# GPS.net
KiCad netlist of a schematic drawn in Altium Designer
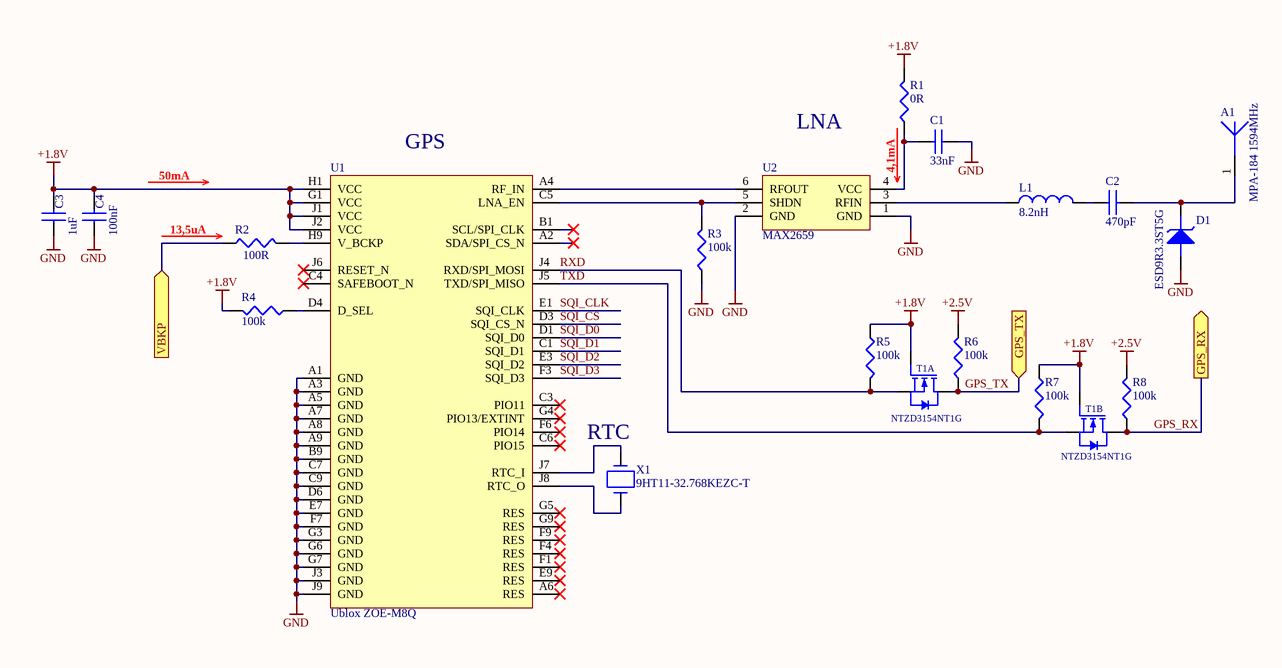
[diagram p0: GPS.SchDoc]

(export (version "E")
  (design (tool "Eeschema 10.0.6"))
  (components
    (comp (ref "A1")
      (value "MPA-184 1594MHz")
      (footprint "MPA-184")
      (description "Antennas Passive GPS/GLONASS Patch Antenna")
      (fields (field (name "MANUFACTURER") "Antenova") (field (name "MANUFACTURER PART NUMBER") "SR42I010-R"))
      (libsource (lib "Passive") (part "ANT - MAXTENA MPA-184 1594MHz"))
    )
    (comp (ref "C1")
      (value "33nF")
      (footprint "CAP0402")
      (description "33 pF, 16 V,  5%, C0G / NP0, MC Series")
      (fields
        (field (name "MANUFACTURER") "Multicomp")
        (field (name "MANUFACTURER PART NUMBER") "MC0402N330J160CT")
      )
      (libsource (lib "Passive") (part "C - 33pF/0402"))
    )
    (comp (ref "C2")
      (value "470pF")
      (footprint "CAP0402")
      (description "470 pF, 50 V, 0402 [1005 Metric], ± 10%, X7R, GRT Series")
      (fields
        (field (name "MANUFACTURER") "Murata")
        (field (name "MANUFACTURER PART NUMBER") "GRT155R71H471KE01D")
      )
      (libsource (lib "Passive") (part "C - 470pF/0402"))
    )
    (comp (ref "C3")
      (value "1uF")
      (footprint "CAP0402")
      (description "CAP CER 1UF 10V 20% X5R 0402")
      (fields
        (field (name "MANUFACTURER") "Murata")
        (field (name "MANUFACTURER PART NUMBER") "GRM155R61A105ME15D")
      )
      (libsource (lib "Passive") (part "C - 1uF/0402"))
    )
    (comp (ref "C4")
      (value "100nF")
      (footprint "CAP0402")
      (description "0.1 F, 16 V,  5%, X5R, MC Series")
      (fields
        (field (name "MANUFACTURER") "Multicomp")
        (field (name "MANUFACTURER PART NUMBER") "MC0402X104J160CT")
      )
      (libsource (lib "Passive") (part "C - 100nF/0402"))
    )
    (comp (ref "D1")
      (value "ESD9R3.3ST5G")
      (footprint "SOD-923")
      (description "TVS Diode, ESD9R Series, Unidirectional, 3.3 V, 7.8 V")
      (fields
        (field (name "MANUFACTURER") "DIODES INC.")
        (field (name "MANUFACTURER PART NUMBER") "1N4148W-7-F.")
      )
      (libsource (lib "Active") (part "D_TVS - ESD9R3.3ST5G"))
    )
    (comp (ref "L1")
      (value "8.2nH")
      (footprint "IND0402")
      (description "High Frequency Inductor, 8.2 nH, LQG15HN Series, 300 mA, 0402 [1005 Metric], Multilayer, 0.33 ohm")
      (fields
        (field (name "MANUFACTURER") "Murata")
        (field (name "MANUFACTURER PART NUMBER") "LQG15HS33NJ02D")
      )
      (libsource (lib "Passive") (part "L - 33nH/0402"))
    )
    (comp (ref "R1")
      (value "0R")
      (footprint "RES0402")
      (description "RESISTOR, 0402, 0R, ANTI SULFURATION")
      (fields
        (field (name "MANUFACTURER") "Multicomp")
        (field (name "MANUFACTURER PART NUMBER") "MCMR04X000PTL")
      )
      (libsource (lib "Passive") (part "R - 0R/0402"))
    )
    (comp (ref "R2")
      (value "100R")
      (footprint "RES0402")
      (description "100 ohm, 50 V, 0402 [1005 Metric], 62.5 mW,  1%")
      (fields
        (field (name "MANUFACTURER") "Multicomp")
        (field (name "MANUFACTURER PART NUMBER") "MCMR04X1000FTL")
      )
      (libsource (lib "Passive") (part "R - 100R/0402"))
    )
    (comp (ref "R3")
      (value "100k")
      (footprint "RES0402")
      (description "100KOHM, 1%, 0.0625W")
      (fields
        (field (name "MANUFACTURER") "Multicomp")
        (field (name "MANUFACTURER PART NUMBER") "MCWR04X1003FTL")
      )
      (libsource (lib "Passive") (part "R - 100k/0402"))
    )
    (comp (ref "R4")
      (value "100k")
      (footprint "RES0402")
      (description "100KOHM, 1%, 0.0625W")
      (fields
        (field (name "MANUFACTURER") "Multicomp")
        (field (name "MANUFACTURER PART NUMBER") "MCWR04X1003FTL")
      )
      (libsource (lib "Passive") (part "R - 100k/0402"))
    )
    (comp (ref "R5")
      (value "100k")
      (footprint "RES0402")
      (description "100KOHM, 1%, 0.0625W")
      (fields
        (field (name "MANUFACTURER") "Multicomp")
        (field (name "MANUFACTURER PART NUMBER") "MCWR04X1003FTL")
      )
      (libsource (lib "Passive") (part "R - 100k/0402"))
    )
    (comp (ref "R6")
      (value "100k")
      (footprint "RES0402")
      (description "100KOHM, 1%, 0.0625W")
      (fields
        (field (name "MANUFACTURER") "Multicomp")
        (field (name "MANUFACTURER PART NUMBER") "MCWR04X1003FTL")
      )
      (libsource (lib "Passive") (part "R - 100k/0402"))
    )
    (comp (ref "R7")
      (value "100k")
      (footprint "RES0402")
      (description "100KOHM, 1%, 0.0625W")
      (fields
        (field (name "MANUFACTURER") "Multicomp")
        (field (name "MANUFACTURER PART NUMBER") "MCWR04X1003FTL")
      )
      (libsource (lib "Passive") (part "R - 100k/0402"))
    )
    (comp (ref "R8")
      (value "100k")
      (footprint "RES0402")
      (description "100KOHM, 1%, 0.0625W")
      (fields
        (field (name "MANUFACTURER") "Multicomp")
        (field (name "MANUFACTURER PART NUMBER") "MCWR04X1003FTL")
      )
      (libsource (lib "Passive") (part "R - 100k/0402"))
    )
    (comp (ref "T1")
      (value "NTZD3154NT1G")
      (footprint "SOT-563")
      (description "Dual MOSFET, Dual N Channel, 540 mA, 20 V, 0.4 ohm, 4.5 V, 1 V")
      (fields (field (name "AUTHOR") "Ciril Golob"))
      (libsource (lib "Active") (part "T_M - NTZD3154NT1G"))
    )
    (comp (ref "U1")
      (value "Ublox ZOE-M8Q")
      (footprint "S-LGA51")
      (description "ZOE-M8 RF Receiver BeiDou, Galileo, GLONASS, GNSS, GPS -160dBm")
      (fields (field (name "MANUFACTURER") "u-blox") (field (name "MANUFACTURER PART NUMBER") "MAX-M8Q-0"))
      (libsource (lib "Active") (part "RF - UBLOX-ZOE-M8B"))
    )
    (comp (ref "U2")
      (value "MAX2659")
      (footprint "uDFN-6")
      (description "RF Amplifier, GPS / GNSS, 20.5 dB Gain / 0.8 dB Noise, 1575.42 MHz, 1.6 V to 3.3 V Supply")
      (fields (field (name "MANUFACTURER") "u-blox") (field (name "MANUFACTURER PART NUMBER") "MAX-M8Q-0"))
      (libsource (lib "Active") (part "RF - MAX2659"))
    )
    (comp (ref "X1")
      (value "9HT11-32.768KEZC-T")
      (footprint "9HT11")
      (description "Crystal, 32.768 kHz, SMD, 2mm x 1.2mm, 9 pF, 10 ppm, 9HT11 Series")
      (fields (field (name "MANUFACTURER") "IQD") (field (name "MANUFACTURER PART NUMBER") "LFXTAL009678"))
      (libsource (lib "Passive") (part "X - 9HT11-32.768KEZC-T"))
    )
  )
  (nets
    (net (code "1") (name "+1.8V") (class "Default")
      (node (ref "C3") (pin "2") (pinfunction "2_2") (pintype "passive"))
      (node (ref "C4") (pin "2") (pinfunction "2_2") (pintype "passive"))
      (node (ref "R1") (pin "2") (pinfunction "2_2") (pintype "passive"))
      (node (ref "R4") (pin "2") (pinfunction "2_2") (pintype "passive"))
      (node (ref "R5") (pin "1") (pinfunction "1_1") (pintype "passive"))
      (node (ref "R7") (pin "1") (pinfunction "1_1") (pintype "passive"))
      (node (ref "T1") (pin "2") (pinfunction "G1_2") (pintype "passive"))
      (node (ref "T1") (pin "5") (pinfunction "G2_5") (pintype "passive"))
      (node (ref "U1") (pin "G1") (pinfunction "VCC_G1") (pintype "passive"))
      (node (ref "U1") (pin "H1") (pinfunction "VCC_H1") (pintype "passive"))
      (node (ref "U1") (pin "J1") (pinfunction "VCC_J1") (pintype "passive"))
      (node (ref "U1") (pin "J2") (pinfunction "VCC_J2") (pintype "passive"))
    )
    (net (code "2") (name "+2.5V") (class "Default")
      (node (ref "R6") (pin "2") (pinfunction "2_2") (pintype "passive"))
      (node (ref "R8") (pin "2") (pinfunction "2_2") (pintype "passive"))
    )
    (net (code "3") (name "/GPS_RX") (class "Default")
      (node (ref "R8") (pin "1") (pinfunction "1_1") (pintype "passive"))
      (node (ref "T1") (pin "3") (pinfunction "D2_3") (pintype "passive"))
    )
    (net (code "4") (name "/GPS_TX") (class "Default")
      (node (ref "R6") (pin "1") (pinfunction "1_1") (pintype "passive"))
      (node (ref "T1") (pin "6") (pinfunction "D1_6") (pintype "passive"))
    )
    (net (code "5") (name "/RXD") (class "Default")
      (node (ref "R5") (pin "2") (pinfunction "2_2") (pintype "passive"))
      (node (ref "T1") (pin "1") (pinfunction "S1_1") (pintype "passive"))
      (node (ref "U1") (pin "J4") (pinfunction "RXD/SPI_MOSI_J4") (pintype "passive"))
    )
    (net (code "6") (name "/SQI_CLK") (class "Default")
      (node (ref "U1") (pin "E1") (pinfunction "SQI_CLK_E1") (pintype "passive"))
    )
    (net (code "7") (name "/SQI_CS") (class "Default")
      (node (ref "U1") (pin "D3") (pinfunction "SQI_CS_N_D3") (pintype "passive"))
    )
    (net (code "8") (name "/SQI_D0") (class "Default")
      (node (ref "U1") (pin "D1") (pinfunction "SQI_D0_D1") (pintype "passive"))
    )
    (net (code "9") (name "/SQI_D1") (class "Default")
      (node (ref "U1") (pin "C1") (pinfunction "SQI_D1_C1") (pintype "passive"))
    )
    (net (code "10") (name "/SQI_D2") (class "Default")
      (node (ref "U1") (pin "E3") (pinfunction "SQI_D2_E3") (pintype "passive"))
    )
    (net (code "11") (name "/SQI_D3") (class "Default")
      (node (ref "U1") (pin "F3") (pinfunction "SQI_D3_F3") (pintype "passive"))
    )
    (net (code "12") (name "/TXD") (class "Default")
      (node (ref "R7") (pin "2") (pinfunction "2_2") (pintype "passive"))
      (node (ref "T1") (pin "4") (pinfunction "S2_4") (pintype "passive"))
      (node (ref "U1") (pin "J5") (pinfunction "TXD/SPI_MISO_J5") (pintype "passive"))
    )
    (net (code "13") (name "/VBKP") (class "Default")
      (node (ref "R2") (pin "1") (pinfunction "1_1") (pintype "passive"))
    )
    (net (code "14") (name "GND") (class "Default")
      (node (ref "C1") (pin "1") (pinfunction "1_1") (pintype "passive"))
      (node (ref "C3") (pin "1") (pinfunction "1_1") (pintype "passive"))
      (node (ref "C4") (pin "1") (pinfunction "1_1") (pintype "passive"))
      (node (ref "D1") (pin "A") (pinfunction "ANODE_A") (pintype "passive"))
      (node (ref "R3") (pin "1") (pinfunction "1_1") (pintype "passive"))
      (node (ref "U1") (pin "A1") (pinfunction "GND_A1") (pintype "passive"))
      (node (ref "U1") (pin "A3") (pinfunction "GND_A3") (pintype "passive"))
      (node (ref "U1") (pin "A5") (pinfunction "GND_A5") (pintype "passive"))
      (node (ref "U1") (pin "A7") (pinfunction "GND_A7") (pintype "passive"))
      (node (ref "U1") (pin "A8") (pinfunction "GND_A8") (pintype "passive"))
      (node (ref "U1") (pin "A9") (pinfunction "GND_A9") (pintype "passive"))
      (node (ref "U1") (pin "B9") (pinfunction "GND_B9") (pintype "passive"))
      (node (ref "U1") (pin "C7") (pinfunction "GND_C7") (pintype "passive"))
      (node (ref "U1") (pin "C9") (pinfunction "GND_C9") (pintype "passive"))
      (node (ref "U1") (pin "D6") (pinfunction "GND_D6") (pintype "passive"))
      (node (ref "U1") (pin "E7") (pinfunction "GND_E7") (pintype "passive"))
      (node (ref "U1") (pin "F7") (pinfunction "GND_F7") (pintype "passive"))
      (node (ref "U1") (pin "G3") (pinfunction "GND_G3") (pintype "passive"))
      (node (ref "U1") (pin "G6") (pinfunction "GND_G6") (pintype "passive"))
      (node (ref "U1") (pin "G7") (pinfunction "GND_G7") (pintype "passive"))
      (node (ref "U1") (pin "J3") (pinfunction "GND_J3") (pintype "passive"))
      (node (ref "U1") (pin "J9") (pinfunction "GND_J9") (pintype "passive"))
      (node (ref "U2") (pin "1") (pinfunction "GND_1") (pintype "passive"))
      (node (ref "U2") (pin "2") (pinfunction "GND_2") (pintype "passive"))
    )
    (net (code "15") (name "Net-(A1-ANT)") (class "Default")
      (node (ref "A1") (pin "1") (pinfunction "ANT_1") (pintype "passive"))
      (node (ref "C2") (pin "2") (pinfunction "2_2") (pintype "passive"))
      (node (ref "D1") (pin "K") (pinfunction "cathode_K") (pintype "passive"))
    )
    (net (code "16") (name "Net-(C2-Pad1)") (class "Default")
      (node (ref "C2") (pin "1") (pinfunction "1_1") (pintype "passive"))
      (node (ref "L1") (pin "2") (pinfunction "2_2") (pintype "passive"))
    )
    (net (code "17") (name "Net-(U1-D_SEL)") (class "Default")
      (node (ref "R4") (pin "1") (pinfunction "1_1") (pintype "passive"))
      (node (ref "U1") (pin "D4") (pinfunction "D_SEL_D4") (pintype "passive"))
    )
    (net (code "18") (name "Net-(U1-LNA_EN)") (class "Default")
      (node (ref "R3") (pin "2") (pinfunction "2_2") (pintype "passive"))
      (node (ref "U1") (pin "C5") (pinfunction "LNA_EN_C5") (pintype "passive"))
      (node (ref "U2") (pin "5") (pinfunction "SHDN_5") (pintype "passive"))
    )
    (net (code "19") (name "Net-(U1-RF_IN)") (class "Default")
      (node (ref "U1") (pin "A4") (pinfunction "RF_IN_A4") (pintype "passive"))
      (node (ref "U2") (pin "6") (pinfunction "RFOUT_6") (pintype "passive"))
    )
    (net (code "20") (name "Net-(U1-RTC_I)") (class "Default")
      (node (ref "U1") (pin "J7") (pinfunction "RTC_I_J7") (pintype "passive"))
      (node (ref "X1") (pin "2") (pinfunction "2_2") (pintype "passive"))
    )
    (net (code "21") (name "Net-(U1-RTC_O)") (class "Default")
      (node (ref "U1") (pin "J8") (pinfunction "RTC_O_J8") (pintype "passive"))
      (node (ref "X1") (pin "1") (pinfunction "1_1") (pintype "passive"))
    )
    (net (code "22") (name "Net-(U1-V_BCKP)") (class "Default")
      (node (ref "R2") (pin "2") (pinfunction "2_2") (pintype "passive"))
      (node (ref "U1") (pin "H9") (pinfunction "V_BCKP_H9") (pintype "passive"))
    )
    (net (code "23") (name "Net-(U2-RFIN)") (class "Default")
      (node (ref "L1") (pin "1") (pinfunction "1_1") (pintype "passive"))
      (node (ref "U2") (pin "3") (pinfunction "RFIN_3") (pintype "passive"))
    )
    (net (code "24") (name "Net-(U2-VCC)") (class "Default")
      (node (ref "C1") (pin "2") (pinfunction "2_2") (pintype "passive"))
      (node (ref "R1") (pin "1") (pinfunction "1_1") (pintype "passive"))
      (node (ref "U2") (pin "4") (pinfunction "VCC_4") (pintype "passive"))
    )
    (net (code "25") (name "unconnected-(U1-PIO11-PadC3)") (class "Default")
      (node (ref "U1") (pin "C3") (pinfunction "PIO11_C3") (pintype "passive+no_connect"))
    )
    (net (code "26") (name "unconnected-(U1-PIO13{slash}EXTINT-PadG4)") (class "Default")
      (node (ref "U1") (pin "G4") (pinfunction "PIO13/EXTINT_G4") (pintype "passive+no_connect"))
    )
    (net (code "27") (name "unconnected-(U1-PIO14-PadF6)") (class "Default")
      (node (ref "U1") (pin "F6") (pinfunction "PIO14_F6") (pintype "passive+no_connect"))
    )
    (net (code "28") (name "unconnected-(U1-PIO15-PadC6)") (class "Default")
      (node (ref "U1") (pin "C6") (pinfunction "PIO15_C6") (pintype "passive+no_connect"))
    )
    (net (code "29") (name "unconnected-(U1-RES-PadA6)") (class "Default")
      (node (ref "U1") (pin "A6") (pinfunction "RES_A6") (pintype "passive+no_connect"))
    )
    (net (code "30") (name "unconnected-(U1-RES-PadE9)") (class "Default")
      (node (ref "U1") (pin "E9") (pinfunction "RES_E9") (pintype "passive+no_connect"))
    )
    (net (code "31") (name "unconnected-(U1-RES-PadF1)") (class "Default")
      (node (ref "U1") (pin "F1") (pinfunction "RES_F1") (pintype "passive+no_connect"))
    )
    (net (code "32") (name "unconnected-(U1-RES-PadF4)") (class "Default")
      (node (ref "U1") (pin "F4") (pinfunction "RES_F4") (pintype "passive+no_connect"))
    )
    (net (code "33") (name "unconnected-(U1-RES-PadF9)") (class "Default")
      (node (ref "U1") (pin "F9") (pinfunction "RES_F9") (pintype "passive+no_connect"))
    )
    (net (code "34") (name "unconnected-(U1-RES-PadG5)") (class "Default")
      (node (ref "U1") (pin "G5") (pinfunction "RES_G5") (pintype "passive+no_connect"))
    )
    (net (code "35") (name "unconnected-(U1-RES-PadG9)") (class "Default")
      (node (ref "U1") (pin "G9") (pinfunction "RES_G9") (pintype "passive+no_connect"))
    )
    (net (code "36") (name "unconnected-(U1-RESET_N-PadJ6)") (class "Default")
      (node (ref "U1") (pin "J6") (pinfunction "RESET_N_J6") (pintype "passive+no_connect"))
    )
    (net (code "37") (name "unconnected-(U1-SAFEBOOT_N-PadC4)") (class "Default")
      (node (ref "U1") (pin "C4") (pinfunction "SAFEBOOT_N_C4") (pintype "passive+no_connect"))
    )
    (net (code "38") (name "unconnected-(U1-SCL{slash}SPI_CLK-PadB1)") (class "Default")
      (node (ref "U1") (pin "B1") (pinfunction "SCL/SPI_CLK_B1") (pintype "passive+no_connect"))
    )
    (net (code "39") (name "unconnected-(U1-SDA{slash}SPI_CS_N-PadA2)") (class "Default")
      (node (ref "U1") (pin "A2") (pinfunction "SDA/SPI_CS_N_A2") (pintype "passive+no_connect"))
    )
  )
)
